# HVSchematic_Rev2.net
KiCad netlist of a schematic drawn in Altium Designer
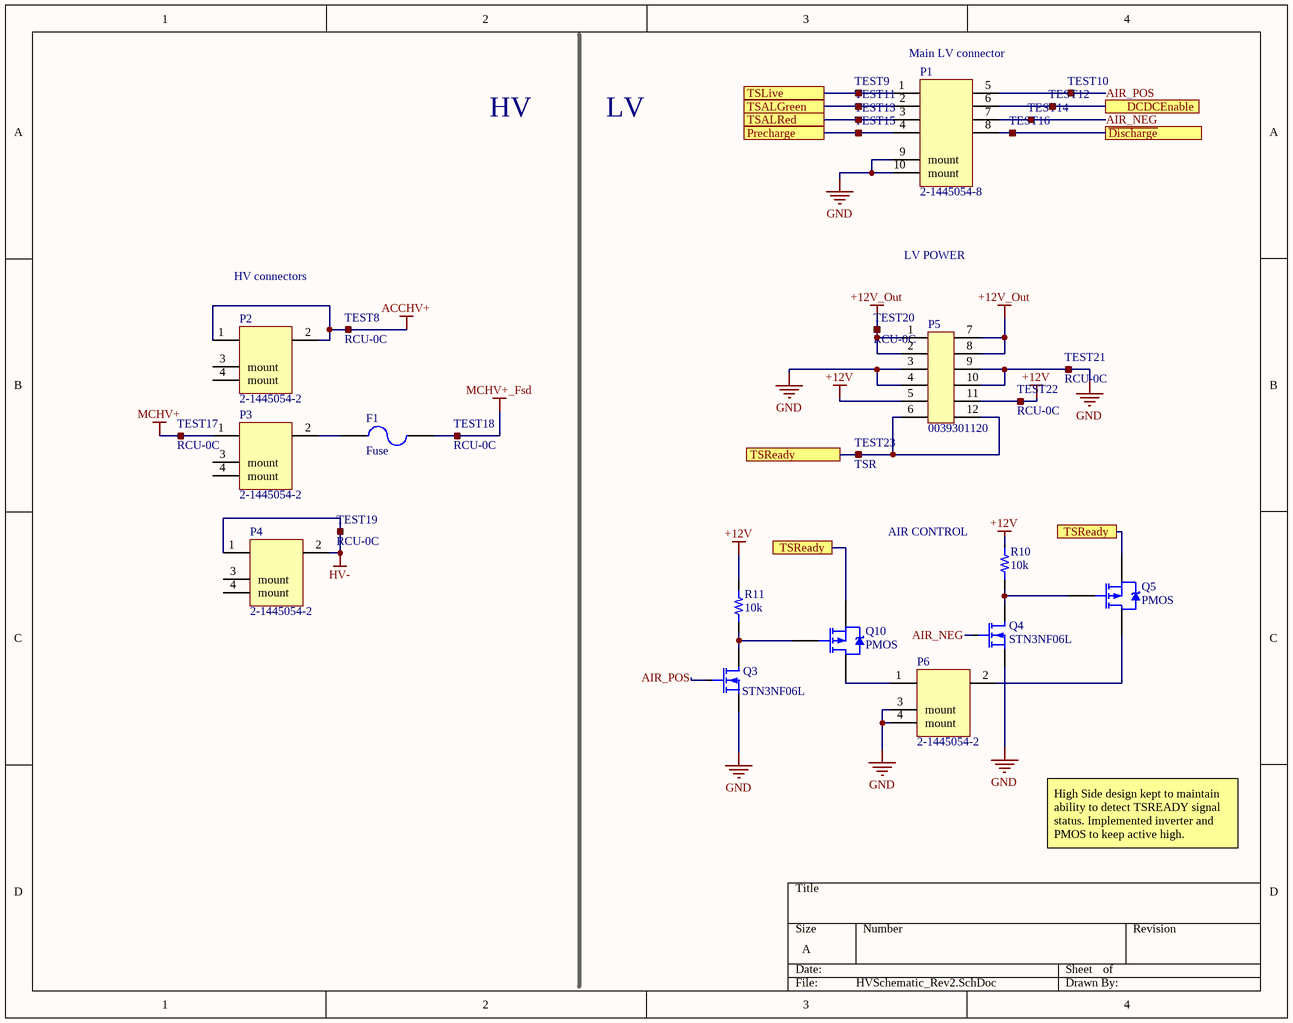
[diagram p0: HVSchematic_Rev2.SchDoc]

(export (version "E")
  (design (tool "Eeschema 10.0.6"))
  (components
    (comp (ref "F1")
      (value "Fuse")
      (footprint "0885004.DR")
      (fields (field (name "MFRPARTNO") "0885004.DR") (field (name "CREATED_BY") "Graydon"))
      (libsource (lib "Altium-Lib") (part "Fuse"))
    )
    (comp (ref "P1")
      (value "2-1445054-8")
      (footprint "2-1445054-8")
      (description "1x8 connector")
      (fields (field (name "CREATED_BY") "Graydon"))
      (libsource (lib "Altium-Lib") (part "2-1445054-8"))
    )
    (comp (ref "P2")
      (value "2-1445054-2")
      (footprint "2-1445054-2")
      (description "1x2 connector")
      (fields (field (name "CREATED_BY") "Graydon") (field (name "UPDATED_BY") "Null"))
      (libsource (lib "Altium-Lib") (part "2-1445054-2"))
    )
    (comp (ref "P3")
      (value "2-1445054-2")
      (footprint "2-1445054-2")
      (description "1x2 connector")
      (fields (field (name "CREATED_BY") "Graydon") (field (name "UPDATED_BY") "Null"))
      (libsource (lib "Altium-Lib") (part "2-1445054-2"))
    )
    (comp (ref "P4")
      (value "2-1445054-2")
      (footprint "2-1445054-2")
      (description "1x2 connector")
      (fields (field (name "CREATED_BY") "Graydon") (field (name "UPDATED_BY") "Null"))
      (libsource (lib "Altium-Lib") (part "2-1445054-2"))
    )
    (comp (ref "P5")
      (value "0039301120")
      (footprint "0039301120")
      (description "Molex Minifit Jr 12p right angle")
      (fields (field (name "CREATED_BY") "Graydon"))
      (libsource (lib "Altium-Lib") (part "0039301120"))
    )
    (comp (ref "P6")
      (value "2-1445054-2")
      (footprint "2-1445054-2")
      (description "1x2 connector")
      (fields (field (name "CREATED_BY") "Graydon") (field (name "UPDATED_BY") "Null"))
      (libsource (lib "Altium-Lib") (part "2-1445054-2"))
    )
    (comp (ref "Q3")
      (value "STN3NF06L")
      (footprint "STN3NF06L")
      (description "MOSFET N-CH 60V 4A SOT223")
      (fields (field (name "CREATED_BY") "Graydon"))
      (libsource (lib "Altium-Lib") (part "STN3NF06L"))
    )
    (comp (ref "Q4")
      (value "STN3NF06L")
      (footprint "STN3NF06L")
      (description "MOSFET N-CH 60V 4A SOT223")
      (fields (field (name "CREATED_BY") "Graydon"))
      (libsource (lib "Altium-Lib") (part "STN3NF06L"))
    )
    (comp (ref "Q5")
      (value "PMOS")
      (footprint "SOT-23 (TO-236)")
      (description "P-Channel 60V 170mA (Ta) 360mW (Ta) Surface Mount SOT-23-3")
      (fields (field (name "MFRPARTNO") "BSS84PH6327XTSA2") (field (name "CREATED_BY") "Angel"))
      (libsource (lib "Altium-Lib") (part "BSS84PH6327XTSA2"))
    )
    (comp (ref "Q10")
      (value "PMOS")
      (footprint "SOT-23 (TO-236)")
      (description "P-Channel 60V 170mA (Ta) 360mW (Ta) Surface Mount SOT-23-3")
      (fields (field (name "MFRPARTNO") "BSS84PH6327XTSA2") (field (name "CREATED_BY") "Angel"))
      (libsource (lib "Altium-Lib") (part "BSS84PH6327XTSA2"))
    )
    (comp (ref "R10")
      (value "10k")
      (footprint "RES 0402/1005")
      (fields
        (field (name "TOLERANCE") "1%")
        (field (name "POWER") "1/10W")
        (field (name "Comment") "Resistor 1.0 0402 1/10W 1%")
        (field (name "CREATED_BY") "Nick Mah")
      )
      (libsource (lib "Altium-Lib") (part "Resistor"))
    )
    (comp (ref "R11")
      (value "10k")
      (footprint "RES 0402/1005")
      (fields
        (field (name "TOLERANCE") "1%")
        (field (name "POWER") "1/10W")
        (field (name "Comment") "Resistor 1.0 0402 1/10W 1%")
        (field (name "CREATED_BY") "Nick Mah")
      )
      (libsource (lib "Altium-Lib") (part "Resistor"))
    )
    (comp (ref "TEST8")
      (value "RCU-0C")
      (footprint "RCU-0C")
      (description "Test point")
      (fields (field (name "CREATED_BY") "Graydon") (field (name "UPDATED_BY") "Null"))
      (libsource (lib "Altium-Lib") (part "RCU-0C"))
    )
    (comp (ref "TEST9")
      (value "TSL")
      (footprint "RCU-0C")
      (description "Test point")
      (fields
        (field (name "MFRPARTNO") "RCU-0C")
        (field (name "CREATED_BY") "Graydon")
        (field (name "UPDATED_BY") "Null")
      )
      (libsource (lib "Altium-Lib") (part "RCU-0C"))
    )
    (comp (ref "TEST10")
      (value "AIR_POS")
      (footprint "RCU-0C")
      (description "Test point")
      (fields
        (field (name "MFRPARTNO") "RCU-0C")
        (field (name "CREATED_BY") "Graydon")
        (field (name "UPDATED_BY") "Null")
      )
      (libsource (lib "Altium-Lib") (part "RCU-0C"))
    )
    (comp (ref "TEST11")
      (value "TSALGreen Out")
      (footprint "RCU-0C")
      (description "Test point")
      (fields
        (field (name "MFRPARTNO") "RCU-0C")
        (field (name "CREATED_BY") "Graydon")
        (field (name "UPDATED_BY") "Null")
      )
      (libsource (lib "Altium-Lib") (part "RCU-0C"))
    )
    (comp (ref "TEST12")
      (value "RCU-0C")
      (footprint "RCU-0C")
      (description "Test point")
      (fields (field (name "CREATED_BY") "Graydon") (field (name "UPDATED_BY") "Null"))
      (libsource (lib "Altium-Lib") (part "RCU-0C"))
    )
    (comp (ref "TEST13")
      (value "TSRED")
      (footprint "RCU-0C")
      (description "Test point")
      (fields
        (field (name "MFRPARTNO") "RCU-0C")
        (field (name "CREATED_BY") "Graydon")
        (field (name "UPDATED_BY") "Null")
      )
      (libsource (lib "Altium-Lib") (part "RCU-0C"))
    )
    (comp (ref "TEST14")
      (value "AIR_NEG")
      (footprint "RCU-0C")
      (description "Test point")
      (fields
        (field (name "MFRPARTNO") "RCU-0C")
        (field (name "CREATED_BY") "Graydon")
        (field (name "UPDATED_BY") "Null")
      )
      (libsource (lib "Altium-Lib") (part "RCU-0C"))
    )
    (comp (ref "TEST15")
      (value "PC")
      (footprint "RCU-0C")
      (description "Test point")
      (fields
        (field (name "MFRPARTNO") "RCU-0C")
        (field (name "CREATED_BY") "Graydon")
        (field (name "UPDATED_BY") "Null")
      )
      (libsource (lib "Altium-Lib") (part "RCU-0C"))
    )
    (comp (ref "TEST16")
      (value "DC")
      (footprint "RCU-0C")
      (description "Test point")
      (fields
        (field (name "MFRPARTNO") "RCU-0C")
        (field (name "CREATED_BY") "Graydon")
        (field (name "UPDATED_BY") "Null")
      )
      (libsource (lib "Altium-Lib") (part "RCU-0C"))
    )
    (comp (ref "TEST17")
      (value "RCU-0C")
      (footprint "RCU-0C")
      (description "Test point")
      (fields (field (name "CREATED_BY") "Graydon") (field (name "UPDATED_BY") "Null"))
      (libsource (lib "Altium-Lib") (part "RCU-0C"))
    )
    (comp (ref "TEST18")
      (value "RCU-0C")
      (footprint "RCU-0C")
      (description "Test point")
      (fields (field (name "CREATED_BY") "Graydon") (field (name "UPDATED_BY") "Null"))
      (libsource (lib "Altium-Lib") (part "RCU-0C"))
    )
    (comp (ref "TEST19")
      (value "RCU-0C")
      (footprint "RCU-0C")
      (description "Test point")
      (fields (field (name "CREATED_BY") "Graydon") (field (name "UPDATED_BY") "Null"))
      (libsource (lib "Altium-Lib") (part "RCU-0C"))
    )
    (comp (ref "TEST20")
      (value "RCU-0C")
      (footprint "RCU-0C")
      (description "Test point")
      (fields (field (name "CREATED_BY") "Graydon") (field (name "UPDATED_BY") "Null"))
      (libsource (lib "Altium-Lib") (part "RCU-0C"))
    )
    (comp (ref "TEST21")
      (value "RCU-0C")
      (footprint "RCU-0C")
      (description "Test point")
      (fields (field (name "CREATED_BY") "Graydon") (field (name "UPDATED_BY") "Null"))
      (libsource (lib "Altium-Lib") (part "RCU-0C"))
    )
    (comp (ref "TEST22")
      (value "RCU-0C")
      (footprint "RCU-0C")
      (description "Test point")
      (fields (field (name "CREATED_BY") "Graydon") (field (name "UPDATED_BY") "Null"))
      (libsource (lib "Altium-Lib") (part "RCU-0C"))
    )
    (comp (ref "TEST23")
      (value "TSR")
      (footprint "RCU-0C")
      (description "Test point")
      (fields
        (field (name "MFRPARTNO") "RCU-0C")
        (field (name "CREATED_BY") "Graydon")
        (field (name "UPDATED_BY") "Null")
      )
      (libsource (lib "Altium-Lib") (part "RCU-0C"))
    )
  )
  (nets
    (net (code "1") (name "+12V") (class "Default")
      (node (ref "P5") (pin "11") (pintype "power_in"))
      (node (ref "P5") (pin "5") (pintype "power_in"))
      (node (ref "R10") (pin "2") (pinfunction "2_2") (pintype "passive"))
      (node (ref "R11") (pin "2") (pinfunction "2_2") (pintype "passive"))
      (node (ref "TEST22") (pin "1") (pintype "passive"))
    )
    (net (code "2") (name "+12V_Out") (class "Default")
      (node (ref "P5") (pin "1") (pintype "power_in"))
      (node (ref "P5") (pin "2") (pintype "power_in"))
      (node (ref "P5") (pin "7") (pintype "power_in"))
      (node (ref "P5") (pin "8") (pintype "power_in"))
      (node (ref "TEST20") (pin "1") (pintype "passive"))
    )
    (net (code "4") (name "/AIR_NEG") (class "Default")
      (node (ref "P1") (pin "7") (pintype "power_in"))
      (node (ref "Q4") (pin "1") (pinfunction "G_1") (pintype "passive"))
      (node (ref "TEST14") (pin "1") (pintype "passive"))
    )
    (net (code "5") (name "/AIR_POS") (class "Default")
      (node (ref "P1") (pin "5") (pintype "power_in"))
      (node (ref "Q3") (pin "1") (pinfunction "G_1") (pintype "passive"))
      (node (ref "TEST10") (pin "1") (pintype "passive"))
    )
    (net (code "6") (name "/DCDCEnable") (class "Default")
      (node (ref "P1") (pin "6") (pintype "power_in"))
      (node (ref "TEST12") (pin "1") (pintype "passive"))
    )
    (net (code "7") (name "/Discharge") (class "Default")
      (node (ref "P1") (pin "8") (pintype "power_in"))
      (node (ref "TEST16") (pin "1") (pintype "passive"))
    )
    (net (code "8") (name "/Precharge") (class "Default")
      (node (ref "P1") (pin "4") (pintype "power_in"))
      (node (ref "TEST15") (pin "1") (pintype "passive"))
    )
    (net (code "9") (name "/TSALGreen") (class "Default")
      (node (ref "P1") (pin "2") (pintype "power_in"))
      (node (ref "TEST11") (pin "1") (pintype "passive"))
    )
    (net (code "10") (name "/TSALRed") (class "Default")
      (node (ref "P1") (pin "3") (pintype "power_in"))
      (node (ref "TEST13") (pin "1") (pintype "passive"))
    )
    (net (code "11") (name "/TSLive") (class "Default")
      (node (ref "P1") (pin "1") (pintype "power_in"))
      (node (ref "TEST9") (pin "1") (pintype "passive"))
    )
    (net (code "12") (name "/TSReady") (class "Default")
      (node (ref "P5") (pin "12") (pintype "power_in"))
      (node (ref "P5") (pin "6") (pintype "power_in"))
      (node (ref "Q10") (pin "2") (pinfunction "S_2") (pintype "passive"))
      (node (ref "Q5") (pin "2") (pinfunction "S_2") (pintype "passive"))
      (node (ref "TEST23") (pin "1") (pintype "passive"))
    )
    (net (code "13") (name "ACCHV+") (class "Default")
      (node (ref "P2") (pin "1") (pintype "power_in"))
      (node (ref "P2") (pin "2") (pintype "power_in"))
      (node (ref "TEST8") (pin "1") (pintype "passive"))
    )
    (net (code "14") (name "GND") (class "Default")
      (node (ref "P1") (pin "10") (pinfunction "mount_10") (pintype "power_in"))
      (node (ref "P1") (pin "9") (pinfunction "mount_9") (pintype "power_in"))
      (node (ref "P5") (pin "10") (pintype "power_in"))
      (node (ref "P5") (pin "3") (pintype "power_in"))
      (node (ref "P5") (pin "4") (pintype "power_in"))
      (node (ref "P5") (pin "9") (pintype "power_in"))
      (node (ref "P6") (pin "3") (pinfunction "mount_3") (pintype "power_in"))
      (node (ref "P6") (pin "4") (pinfunction "mount_4") (pintype "power_in"))
      (node (ref "Q3") (pin "3") (pinfunction "S_3") (pintype "passive"))
      (node (ref "Q4") (pin "3") (pinfunction "S_3") (pintype "passive"))
      (node (ref "TEST21") (pin "1") (pintype "passive"))
    )
    (net (code "15") (name "HV-") (class "Default")
      (node (ref "P4") (pin "1") (pintype "power_in"))
      (node (ref "P4") (pin "2") (pintype "power_in"))
      (node (ref "TEST19") (pin "1") (pintype "passive"))
    )
    (net (code "16") (name "MCHV+") (class "Default")
      (node (ref "P3") (pin "1") (pintype "power_in"))
      (node (ref "TEST17") (pin "1") (pintype "passive"))
    )
    (net (code "17") (name "MCHV+_Fsd") (class "Default")
      (node (ref "F1") (pin "2") (pinfunction "2_2") (pintype "passive"))
      (node (ref "TEST18") (pin "1") (pintype "passive"))
    )
    (net (code "18") (name "Net-(F1-Pad1)") (class "Default")
      (node (ref "F1") (pin "1") (pinfunction "1_1") (pintype "passive"))
      (node (ref "P3") (pin "2") (pintype "power_in"))
    )
    (net (code "19") (name "Net-(Q4-D)") (class "Default")
      (node (ref "Q4") (pin "2") (pinfunction "D_2") (pintype "passive"))
      (node (ref "Q5") (pin "1") (pinfunction "G_1") (pintype "passive"))
      (node (ref "R10") (pin "1") (pinfunction "1_1") (pintype "passive"))
    )
    (net (code "20") (name "Net-(Q5-D)") (class "Default")
      (node (ref "P6") (pin "2") (pintype "power_in"))
      (node (ref "Q5") (pin "3") (pinfunction "D_3") (pintype "passive"))
    )
    (net (code "21") (name "Net-(Q10-D)") (class "Default")
      (node (ref "P6") (pin "1") (pintype "power_in"))
      (node (ref "Q10") (pin "3") (pinfunction "D_3") (pintype "passive"))
    )
    (net (code "22") (name "Net-(Q10-G)") (class "Default")
      (node (ref "Q10") (pin "1") (pinfunction "G_1") (pintype "passive"))
      (node (ref "Q3") (pin "2") (pinfunction "D_2") (pintype "passive"))
      (node (ref "R11") (pin "1") (pinfunction "1_1") (pintype "passive"))
    )
    (net (code "23") (name "unconnected-(P2-mount-Pad3)") (class "Default")
      (node (ref "P2") (pin "3") (pinfunction "mount_3") (pintype "power_in"))
    )
    (net (code "24") (name "unconnected-(P2-mount-Pad4)") (class "Default")
      (node (ref "P2") (pin "4") (pinfunction "mount_4") (pintype "power_in"))
    )
    (net (code "25") (name "unconnected-(P3-mount-Pad3)") (class "Default")
      (node (ref "P3") (pin "3") (pinfunction "mount_3") (pintype "power_in"))
    )
    (net (code "26") (name "unconnected-(P3-mount-Pad4)") (class "Default")
      (node (ref "P3") (pin "4") (pinfunction "mount_4") (pintype "power_in"))
    )
    (net (code "27") (name "unconnected-(P4-mount-Pad3)") (class "Default")
      (node (ref "P4") (pin "3") (pinfunction "mount_3") (pintype "power_in"))
    )
    (net (code "28") (name "unconnected-(P4-mount-Pad4)") (class "Default")
      (node (ref "P4") (pin "4") (pinfunction "mount_4") (pintype "power_in"))
    )
  )
)
